# Schematic.net
KiCad netlist of a schematic drawn in EasyEDA
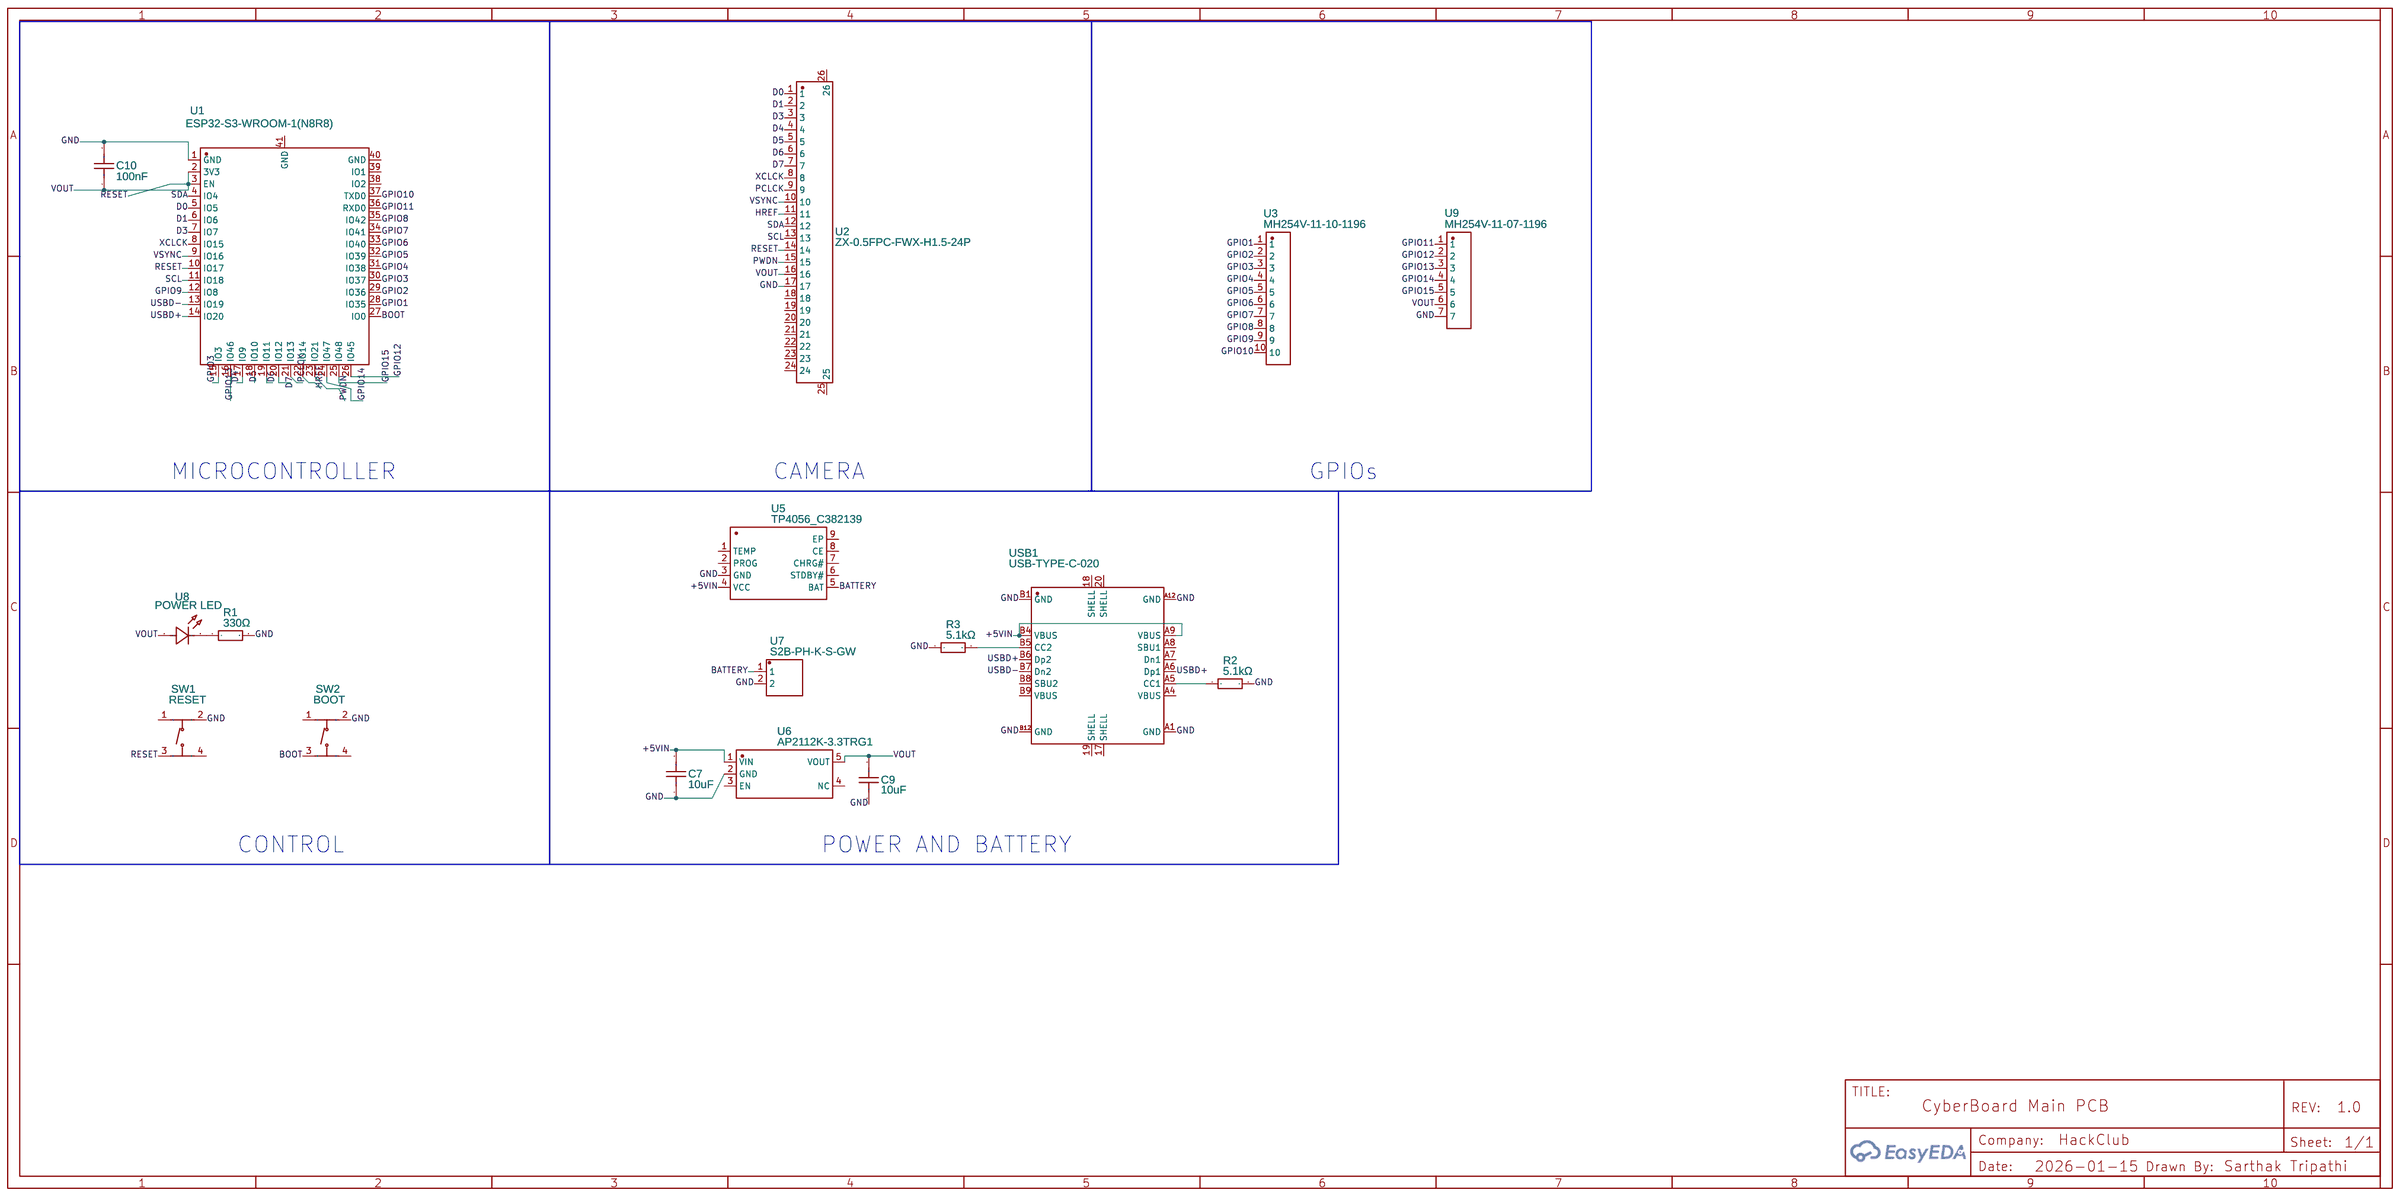
[diagram p0: schematic sheet]

(export (version "E")
  (design (tool "Eeschema 10.0.6"))
  (components
    (comp (ref "C7")
      (value "10uF")
      (fields
        (field (name "Manufacturer Part") "GRM21BR61H106KE43L")
        (field (name "Manufacturer") "muRata(村田)")
      )
      (libsource (lib "") (part "GRM21BR61H106KE43L"))
    )
    (comp (ref "C9")
      (value "10uF")
      (fields
        (field (name "Manufacturer Part") "GRM21BR61H106KE43L")
        (field (name "Manufacturer") "muRata(村田)")
      )
      (libsource (lib "") (part "GRM21BR61H106KE43L"))
    )
    (comp (ref "C10")
      (value "100nF")
      (fields
        (field (name "Manufacturer Part") "CC0603KRX7R9BB104")
        (field (name "Manufacturer") "YAGEO(国巨)")
      )
      (libsource (lib "") (part "CC0603KRX7R9BB104"))
    )
    (comp (ref "R1")
      (value "330Ω")
      (fields
        (field (name "Manufacturer Part") "0603WAF3300T5E")
        (field (name "Manufacturer") "UNI-ROYAL(厚声)")
      )
      (libsource (lib "") (part "0603WAF3300T5E"))
    )
    (comp (ref "R2")
      (value "5.1kΩ")
      (fields
        (field (name "Manufacturer Part") "MF1/4W-5.1KΩ±1% T")
        (field (name "Manufacturer") "CCO(千志电子)")
      )
      (libsource (lib "") (part "MF1/4W-5.1KΩ±1% T52"))
    )
    (comp (ref "R3")
      (value "5.1kΩ")
      (fields
        (field (name "Manufacturer Part") "MF1/4W-5.1KΩ±1% T")
        (field (name "Manufacturer") "CCO(千志电子)")
      )
      (libsource (lib "") (part "MF1/4W-5.1KΩ±1% T52"))
    )
    (comp (ref "SW1")
      (value "RESET")
      (fields
        (field (name "Manufacturer Part") "TS-1187A-B-A-B")
        (field (name "Manufacturer") "XKB Connection(中国星坤)")
      )
      (libsource (lib "") (part "TS-1187A-B-A-B"))
    )
    (comp (ref "SW2")
      (value "BOOT")
      (fields
        (field (name "Manufacturer Part") "TS-1187A-B-A-B")
        (field (name "Manufacturer") "XKB Connection(中国星坤)")
      )
      (libsource (lib "") (part "TS-1187A-B-A-B"))
    )
    (comp (ref "U1")
      (value "ESP32-S3-WROOM-1(N8R8)")
      (fields
        (field (name "Manufacturer Part") "ESP32-S3-WROOM-1-N8R8")
        (field (name "Manufacturer") "ESPRESSIF(乐鑫)")
      )
      (libsource (lib "") (part "ESP32-S3-WROOM-1(N8R8)"))
    )
    (comp (ref "U2")
      (value "ZX-0.5FPC-FWX-H1.5-24P")
      (fields (field (name "Manufacturer") "Megastar(兆星)"))
      (libsource (lib "") (part "ZX-0.5FPC-FWX-H1.5-24P"))
    )
    (comp (ref "U3")
      (value "MH254V-11-10-1196")
      (fields (field (name "Manufacturer") "XFCN(兴飞)"))
      (libsource (lib "") (part "MH254V-11-10-1196"))
    )
    (comp (ref "U5")
      (value "TP4056_C382139")
      (fields (field (name "Manufacturer Part") "TP4056") (field (name "Manufacturer") "TPOWER(天源)"))
      (libsource (lib "") (part "TP4056_C382139"))
    )
    (comp (ref "U6")
      (value "AP2112K-3.3TRG1")
      (fields (field (name "Manufacturer") "DIODES(美台)"))
      (libsource (lib "") (part "AP2112K-3.3TRG1"))
    )
    (comp (ref "U7")
      (value "S2B-PH-K-S-GW")
      (fields (field (name "Manufacturer") "JST"))
      (libsource (lib "") (part "S2B-PH-K-S-GW"))
    )
    (comp (ref "U8")
      (value "POWER LED")
      (fields (field (name "Manufacturer Part") "YLED0603G") (field (name "Manufacturer") "YONGYUTAI(永裕泰)"))
      (libsource (lib "") (part "YLED0603G"))
    )
    (comp (ref "U9")
      (value "MH254V-11-07-1196")
      (fields (field (name "Manufacturer") "XFCN(兴飞)"))
      (libsource (lib "") (part "MH254V-11-07-1196"))
    )
    (comp (ref "USB1")
      (value "USB-TYPE-C-020")
      (fields (field (name "Manufacturer") "DEALON(德艺隆)"))
      (libsource (lib "") (part "USB-TYPE-C-020"))
    )
  )
  (nets
    (net (code "1") (name "/+5VIN") (class "Default")
      (node (ref "C7") (pin "2") (pinfunction "2_2") (pintype "unspecified"))
      (node (ref "U5") (pin "4") (pinfunction "VCC_4") (pintype "unspecified"))
      (node (ref "U6") (pin "1") (pinfunction "VIN_1") (pintype "unspecified"))
      (node (ref "USB1") (pin "A9") (pinfunction "VBUS_A9") (pintype "unspecified"))
      (node (ref "USB1") (pin "B4") (pinfunction "VBUS_B4") (pintype "unspecified"))
    )
    (net (code "2") (name "/BATTERY") (class "Default")
      (node (ref "U5") (pin "5") (pinfunction "BAT_5") (pintype "unspecified"))
      (node (ref "U7") (pin "1") (pinfunction "1_1") (pintype "unspecified"))
    )
    (net (code "3") (name "/BOOT") (class "Default")
      (node (ref "SW2") (pin "3") (pinfunction "C_3") (pintype "unspecified"))
      (node (ref "U1") (pin "27") (pinfunction "IO0_27") (pintype "unspecified"))
    )
    (net (code "4") (name "/D0") (class "Default")
      (node (ref "U1") (pin "5") (pinfunction "IO5_5") (pintype "unspecified"))
      (node (ref "U2") (pin "1") (pinfunction "1_1") (pintype "unspecified"))
    )
    (net (code "5") (name "/D1") (class "Default")
      (node (ref "U1") (pin "6") (pinfunction "IO6_6") (pintype "unspecified"))
      (node (ref "U2") (pin "2") (pinfunction "2_2") (pintype "unspecified"))
    )
    (net (code "6") (name "/D3") (class "Default")
      (node (ref "U1") (pin "7") (pinfunction "IO7_7") (pintype "unspecified"))
      (node (ref "U2") (pin "3") (pinfunction "3_3") (pintype "unspecified"))
    )
    (net (code "7") (name "/D4") (class "Default")
      (node (ref "U1") (pin "17") (pinfunction "IO9_17") (pintype "unspecified"))
      (node (ref "U2") (pin "4") (pinfunction "4_4") (pintype "unspecified"))
    )
    (net (code "8") (name "/D5") (class "Default")
      (node (ref "U1") (pin "18") (pinfunction "IO10_18") (pintype "unspecified"))
      (node (ref "U2") (pin "5") (pinfunction "5_5") (pintype "unspecified"))
    )
    (net (code "9") (name "/D6") (class "Default")
      (node (ref "U1") (pin "19") (pinfunction "IO11_19") (pintype "unspecified"))
      (node (ref "U2") (pin "6") (pinfunction "6_6") (pintype "unspecified"))
    )
    (net (code "10") (name "/D7") (class "Default")
      (node (ref "U2") (pin "7") (pinfunction "7_7") (pintype "unspecified"))
    )
    (net (code "11") (name "/GND") (class "Default")
      (node (ref "C10") (pin "2") (pinfunction "2_2") (pintype "unspecified"))
      (node (ref "C7") (pin "1") (pinfunction "1_1") (pintype "unspecified"))
      (node (ref "C9") (pin "1") (pinfunction "1_1") (pintype "unspecified"))
      (node (ref "R1") (pin "2") (pinfunction "2_2") (pintype "input"))
      (node (ref "R2") (pin "2") (pinfunction "2_2") (pintype "unspecified"))
      (node (ref "R3") (pin "1") (pinfunction "1_1") (pintype "unspecified"))
      (node (ref "SW1") (pin "2") (pinfunction "B_2") (pintype "unspecified"))
      (node (ref "SW2") (pin "2") (pinfunction "B_2") (pintype "unspecified"))
      (node (ref "U1") (pin "1") (pinfunction "GND_1") (pintype "unspecified"))
      (node (ref "U2") (pin "17") (pinfunction "17_17") (pintype "unspecified"))
      (node (ref "U5") (pin "3") (pinfunction "GND_3") (pintype "unspecified"))
      (node (ref "U6") (pin "2") (pinfunction "GND_2") (pintype "unspecified"))
      (node (ref "U7") (pin "2") (pinfunction "2_2") (pintype "unspecified"))
      (node (ref "U9") (pin "7") (pinfunction "7_7") (pintype "unspecified"))
      (node (ref "USB1") (pin "A1") (pinfunction "GND_A1") (pintype "unspecified"))
      (node (ref "USB1") (pin "A12") (pinfunction "GND_A12") (pintype "unspecified"))
      (node (ref "USB1") (pin "B1") (pinfunction "GND_B1") (pintype "unspecified"))
      (node (ref "USB1") (pin "B12") (pinfunction "GND_B12") (pintype "unspecified"))
    )
    (net (code "12") (name "/GPIO1") (class "Default")
      (node (ref "U1") (pin "28") (pinfunction "IO35_28") (pintype "unspecified"))
      (node (ref "U3") (pin "1") (pinfunction "1_1") (pintype "unspecified"))
    )
    (net (code "13") (name "/GPIO2") (class "Default")
      (node (ref "U1") (pin "29") (pinfunction "IO36_29") (pintype "unspecified"))
      (node (ref "U3") (pin "2") (pinfunction "2_2") (pintype "unspecified"))
    )
    (net (code "14") (name "/GPIO3") (class "Default")
      (node (ref "U1") (pin "15") (pinfunction "IO3_15") (pintype "unspecified"))
      (node (ref "U1") (pin "30") (pinfunction "IO37_30") (pintype "unspecified"))
      (node (ref "U3") (pin "3") (pinfunction "3_3") (pintype "unspecified"))
    )
    (net (code "15") (name "/GPIO4") (class "Default")
      (node (ref "U1") (pin "31") (pinfunction "IO38_31") (pintype "unspecified"))
      (node (ref "U3") (pin "4") (pinfunction "4_4") (pintype "unspecified"))
    )
    (net (code "16") (name "/GPIO5") (class "Default")
      (node (ref "U1") (pin "32") (pinfunction "IO39_32") (pintype "unspecified"))
      (node (ref "U3") (pin "5") (pinfunction "5_5") (pintype "unspecified"))
    )
    (net (code "17") (name "/GPIO6") (class "Default")
      (node (ref "U1") (pin "33") (pinfunction "IO40_33") (pintype "unspecified"))
      (node (ref "U3") (pin "6") (pinfunction "6_6") (pintype "unspecified"))
    )
    (net (code "18") (name "/GPIO7") (class "Default")
      (node (ref "U1") (pin "34") (pinfunction "IO41_34") (pintype "unspecified"))
      (node (ref "U3") (pin "7") (pinfunction "7_7") (pintype "unspecified"))
    )
    (net (code "19") (name "/GPIO8") (class "Default")
      (node (ref "U1") (pin "35") (pinfunction "IO42_35") (pintype "unspecified"))
      (node (ref "U3") (pin "8") (pinfunction "8_8") (pintype "unspecified"))
    )
    (net (code "20") (name "/GPIO9") (class "Default")
      (node (ref "U1") (pin "12") (pinfunction "IO8_12") (pintype "unspecified"))
      (node (ref "U3") (pin "9") (pinfunction "9_9") (pintype "unspecified"))
    )
    (net (code "21") (name "/GPIO10") (class "Default")
      (node (ref "U1") (pin "37") (pinfunction "TXD0_37") (pintype "unspecified"))
      (node (ref "U3") (pin "10") (pinfunction "10_10") (pintype "unspecified"))
    )
    (net (code "22") (name "/GPIO11") (class "Default")
      (node (ref "U1") (pin "36") (pinfunction "RXD0_36") (pintype "unspecified"))
      (node (ref "U9") (pin "1") (pinfunction "1_1") (pintype "unspecified"))
    )
    (net (code "23") (name "/GPIO12") (class "Default")
      (node (ref "U1") (pin "26") (pinfunction "IO45_26") (pintype "unspecified"))
      (node (ref "U9") (pin "2") (pinfunction "2_2") (pintype "unspecified"))
    )
    (net (code "24") (name "/GPIO13") (class "Default")
      (node (ref "U1") (pin "16") (pinfunction "IO46_16") (pintype "unspecified"))
      (node (ref "U9") (pin "3") (pinfunction "3_3") (pintype "unspecified"))
    )
    (net (code "25") (name "/GPIO14") (class "Default")
      (node (ref "U1") (pin "24") (pinfunction "IO47_24") (pintype "unspecified"))
      (node (ref "U9") (pin "4") (pinfunction "4_4") (pintype "unspecified"))
    )
    (net (code "26") (name "/GPIO15") (class "Default")
      (node (ref "U1") (pin "25") (pinfunction "IO48_25") (pintype "unspecified"))
      (node (ref "U9") (pin "5") (pinfunction "5_5") (pintype "unspecified"))
    )
    (net (code "27") (name "/HREF") (class "Default")
      (node (ref "U1") (pin "22") (pinfunction "IO14_22") (pintype "unspecified"))
      (node (ref "U2") (pin "11") (pinfunction "11_11") (pintype "unspecified"))
    )
    (net (code "28") (name "/PCLCK") (class "Default")
      (node (ref "U1") (pin "21") (pinfunction "IO13_21") (pintype "unspecified"))
      (node (ref "U2") (pin "9") (pinfunction "9_9") (pintype "unspecified"))
    )
    (net (code "29") (name "/PWDN") (class "Default")
      (node (ref "U1") (pin "23") (pinfunction "IO21_23") (pintype "unspecified"))
      (node (ref "U2") (pin "15") (pinfunction "15_15") (pintype "unspecified"))
    )
    (net (code "30") (name "/RESET") (class "Default")
      (node (ref "C10") (pin "1") (pinfunction "1_1") (pintype "unspecified"))
      (node (ref "C9") (pin "2") (pinfunction "2_2") (pintype "unspecified"))
      (node (ref "SW1") (pin "3") (pinfunction "C_3") (pintype "unspecified"))
      (node (ref "U1") (pin "10") (pinfunction "IO17_10") (pintype "unspecified"))
      (node (ref "U1") (pin "2") (pinfunction "3V3_2") (pintype "unspecified"))
      (node (ref "U1") (pin "3") (pinfunction "EN_3") (pintype "unspecified"))
      (node (ref "U2") (pin "14") (pinfunction "14_14") (pintype "unspecified"))
      (node (ref "U2") (pin "16") (pinfunction "16_16") (pintype "unspecified"))
      (node (ref "U6") (pin "5") (pinfunction "VOUT_5") (pintype "unspecified"))
      (node (ref "U8") (pin "1") (pinfunction "+_1") (pintype "unspecified"))
      (node (ref "U9") (pin "6") (pinfunction "6_6") (pintype "unspecified"))
    )
    (net (code "31") (name "/SCL") (class "Default")
      (node (ref "U1") (pin "11") (pinfunction "IO18_11") (pintype "unspecified"))
      (node (ref "U2") (pin "13") (pinfunction "13_13") (pintype "unspecified"))
    )
    (net (code "32") (name "/SDA") (class "Default")
      (node (ref "U1") (pin "4") (pinfunction "IO4_4") (pintype "unspecified"))
      (node (ref "U2") (pin "12") (pinfunction "12_12") (pintype "unspecified"))
    )
    (net (code "33") (name "/USBD+") (class "Default")
      (node (ref "U1") (pin "14") (pinfunction "IO20_14") (pintype "unspecified"))
      (node (ref "USB1") (pin "A6") (pinfunction "Dp1_A6") (pintype "unspecified"))
      (node (ref "USB1") (pin "B6") (pinfunction "Dp2_B6") (pintype "unspecified"))
    )
    (net (code "34") (name "/USBD-") (class "Default")
      (node (ref "U1") (pin "13") (pinfunction "IO19_13") (pintype "unspecified"))
      (node (ref "USB1") (pin "B7") (pinfunction "Dn2_B7") (pintype "unspecified"))
    )
    (net (code "35") (name "/VSYNC") (class "Default")
      (node (ref "U1") (pin "9") (pinfunction "IO16_9") (pintype "unspecified"))
      (node (ref "U2") (pin "10") (pinfunction "10_10") (pintype "unspecified"))
    )
    (net (code "36") (name "/XCLCK") (class "Default")
      (node (ref "U1") (pin "8") (pinfunction "IO15_8") (pintype "unspecified"))
      (node (ref "U2") (pin "8") (pinfunction "8_8") (pintype "unspecified"))
    )
    (net (code "37") (name "Net-(U8--)") (class "Default")
      (node (ref "R1") (pin "1") (pinfunction "1_1") (pintype "input"))
      (node (ref "U8") (pin "2") (pinfunction "-_2") (pintype "unspecified"))
    )
    (net (code "38") (name "Net-(USB1-CC1)") (class "Default")
      (node (ref "R2") (pin "1") (pinfunction "1_1") (pintype "unspecified"))
      (node (ref "USB1") (pin "A5") (pinfunction "CC1_A5") (pintype "unspecified"))
    )
    (net (code "39") (name "Net-(USB1-CC2)") (class "Default")
      (node (ref "R3") (pin "2") (pinfunction "2_2") (pintype "unspecified"))
      (node (ref "USB1") (pin "B5") (pinfunction "CC2_B5") (pintype "unspecified"))
    )
    (net (code "40") (name "unconnected-(SW1-A-Pad1)") (class "Default")
      (node (ref "SW1") (pin "1") (pinfunction "A_1") (pintype "unspecified"))
    )
    (net (code "41") (name "unconnected-(SW1-D-Pad4)") (class "Default")
      (node (ref "SW1") (pin "4") (pinfunction "D_4") (pintype "unspecified"))
    )
    (net (code "42") (name "unconnected-(SW2-A-Pad1)") (class "Default")
      (node (ref "SW2") (pin "1") (pinfunction "A_1") (pintype "unspecified"))
    )
    (net (code "43") (name "unconnected-(SW2-D-Pad4)") (class "Default")
      (node (ref "SW2") (pin "4") (pinfunction "D_4") (pintype "unspecified"))
    )
    (net (code "44") (name "unconnected-(U1-GND-Pad40)") (class "Default")
      (node (ref "U1") (pin "40") (pinfunction "GND_40") (pintype "unspecified"))
    )
    (net (code "45") (name "unconnected-(U1-GND-Pad41)") (class "Default")
      (node (ref "U1") (pin "41") (pinfunction "GND_41") (pintype "unspecified"))
    )
    (net (code "46") (name "unconnected-(U1-IO1-Pad39)") (class "Default")
      (node (ref "U1") (pin "39") (pinfunction "IO1_39") (pintype "unspecified"))
    )
    (net (code "47") (name "unconnected-(U1-IO2-Pad38)") (class "Default")
      (node (ref "U1") (pin "38") (pinfunction "IO2_38") (pintype "unspecified"))
    )
    (net (code "48") (name "unconnected-(U1-IO12-Pad20)") (class "Default")
      (node (ref "U1") (pin "20") (pinfunction "IO12_20") (pintype "unspecified"))
    )
    (net (code "49") (name "unconnected-(U2-Pad18)") (class "Default")
      (node (ref "U2") (pin "18") (pinfunction "18_18") (pintype "unspecified"))
    )
    (net (code "50") (name "unconnected-(U2-Pad19)") (class "Default")
      (node (ref "U2") (pin "19") (pinfunction "19_19") (pintype "unspecified"))
    )
    (net (code "51") (name "unconnected-(U2-Pad20)") (class "Default")
      (node (ref "U2") (pin "20") (pinfunction "20_20") (pintype "unspecified"))
    )
    (net (code "52") (name "unconnected-(U2-Pad21)") (class "Default")
      (node (ref "U2") (pin "21") (pinfunction "21_21") (pintype "unspecified"))
    )
    (net (code "53") (name "unconnected-(U2-Pad22)") (class "Default")
      (node (ref "U2") (pin "22") (pinfunction "22_22") (pintype "unspecified"))
    )
    (net (code "54") (name "unconnected-(U2-Pad23)") (class "Default")
      (node (ref "U2") (pin "23") (pinfunction "23_23") (pintype "unspecified"))
    )
    (net (code "55") (name "unconnected-(U2-Pad24)") (class "Default")
      (node (ref "U2") (pin "24") (pinfunction "24_24") (pintype "unspecified"))
    )
    (net (code "56") (name "unconnected-(U2-Pad25)") (class "Default")
      (node (ref "U2") (pin "25") (pinfunction "25_25") (pintype "unspecified"))
    )
    (net (code "57") (name "unconnected-(U2-Pad26)") (class "Default")
      (node (ref "U2") (pin "26") (pinfunction "26_26") (pintype "unspecified"))
    )
    (net (code "58") (name "unconnected-(U5-CE-Pad8)") (class "Default")
      (node (ref "U5") (pin "8") (pinfunction "CE_8") (pintype "unspecified"))
    )
    (net (code "59") (name "unconnected-(U5-CHRG#-Pad7)") (class "Default")
      (node (ref "U5") (pin "7") (pinfunction "CHRG#_7") (pintype "unspecified"))
    )
    (net (code "60") (name "unconnected-(U5-EP-Pad9)") (class "Default")
      (node (ref "U5") (pin "9") (pinfunction "EP_9") (pintype "unspecified"))
    )
    (net (code "61") (name "unconnected-(U5-PROG-Pad2)") (class "Default")
      (node (ref "U5") (pin "2") (pinfunction "PROG_2") (pintype "unspecified"))
    )
    (net (code "62") (name "unconnected-(U5-STDBY#-Pad6)") (class "Default")
      (node (ref "U5") (pin "6") (pinfunction "STDBY#_6") (pintype "unspecified"))
    )
    (net (code "63") (name "unconnected-(U5-TEMP-Pad1)") (class "Default")
      (node (ref "U5") (pin "1") (pinfunction "TEMP_1") (pintype "unspecified"))
    )
    (net (code "64") (name "unconnected-(U6-EN-Pad3)") (class "Default")
      (node (ref "U6") (pin "3") (pinfunction "EN_3") (pintype "unspecified"))
    )
    (net (code "65") (name "unconnected-(U6-NC-Pad4)") (class "Default")
      (node (ref "U6") (pin "4") (pinfunction "NC_4") (pintype "unspecified"))
    )
    (net (code "66") (name "unconnected-(USB1-Dn1-PadA7)") (class "Default")
      (node (ref "USB1") (pin "A7") (pinfunction "Dn1_A7") (pintype "unspecified"))
    )
    (net (code "67") (name "unconnected-(USB1-SBU1-PadA8)") (class "Default")
      (node (ref "USB1") (pin "A8") (pinfunction "SBU1_A8") (pintype "unspecified"))
    )
    (net (code "68") (name "unconnected-(USB1-SBU2-PadB8)") (class "Default")
      (node (ref "USB1") (pin "B8") (pinfunction "SBU2_B8") (pintype "unspecified"))
    )
    (net (code "69") (name "unconnected-(USB1-SHELL-Pad17)") (class "Default")
      (node (ref "USB1") (pin "17") (pinfunction "SHELL_17") (pintype "unspecified"))
    )
    (net (code "70") (name "unconnected-(USB1-SHELL-Pad18)") (class "Default")
      (node (ref "USB1") (pin "18") (pinfunction "SHELL_18") (pintype "unspecified"))
    )
    (net (code "71") (name "unconnected-(USB1-SHELL-Pad19)") (class "Default")
      (node (ref "USB1") (pin "19") (pinfunction "SHELL_19") (pintype "unspecified"))
    )
    (net (code "72") (name "unconnected-(USB1-SHELL-Pad20)") (class "Default")
      (node (ref "USB1") (pin "20") (pinfunction "SHELL_20") (pintype "unspecified"))
    )
    (net (code "73") (name "unconnected-(USB1-VBUS-PadA4)") (class "Default")
      (node (ref "USB1") (pin "A4") (pinfunction "VBUS_A4") (pintype "unspecified"))
    )
    (net (code "74") (name "unconnected-(USB1-VBUS-PadB9)") (class "Default")
      (node (ref "USB1") (pin "B9") (pinfunction "VBUS_B9") (pintype "unspecified"))
    )
  )
)
